# triode_control_board.net
KiCad netlist of a schematic drawn in EAGLE
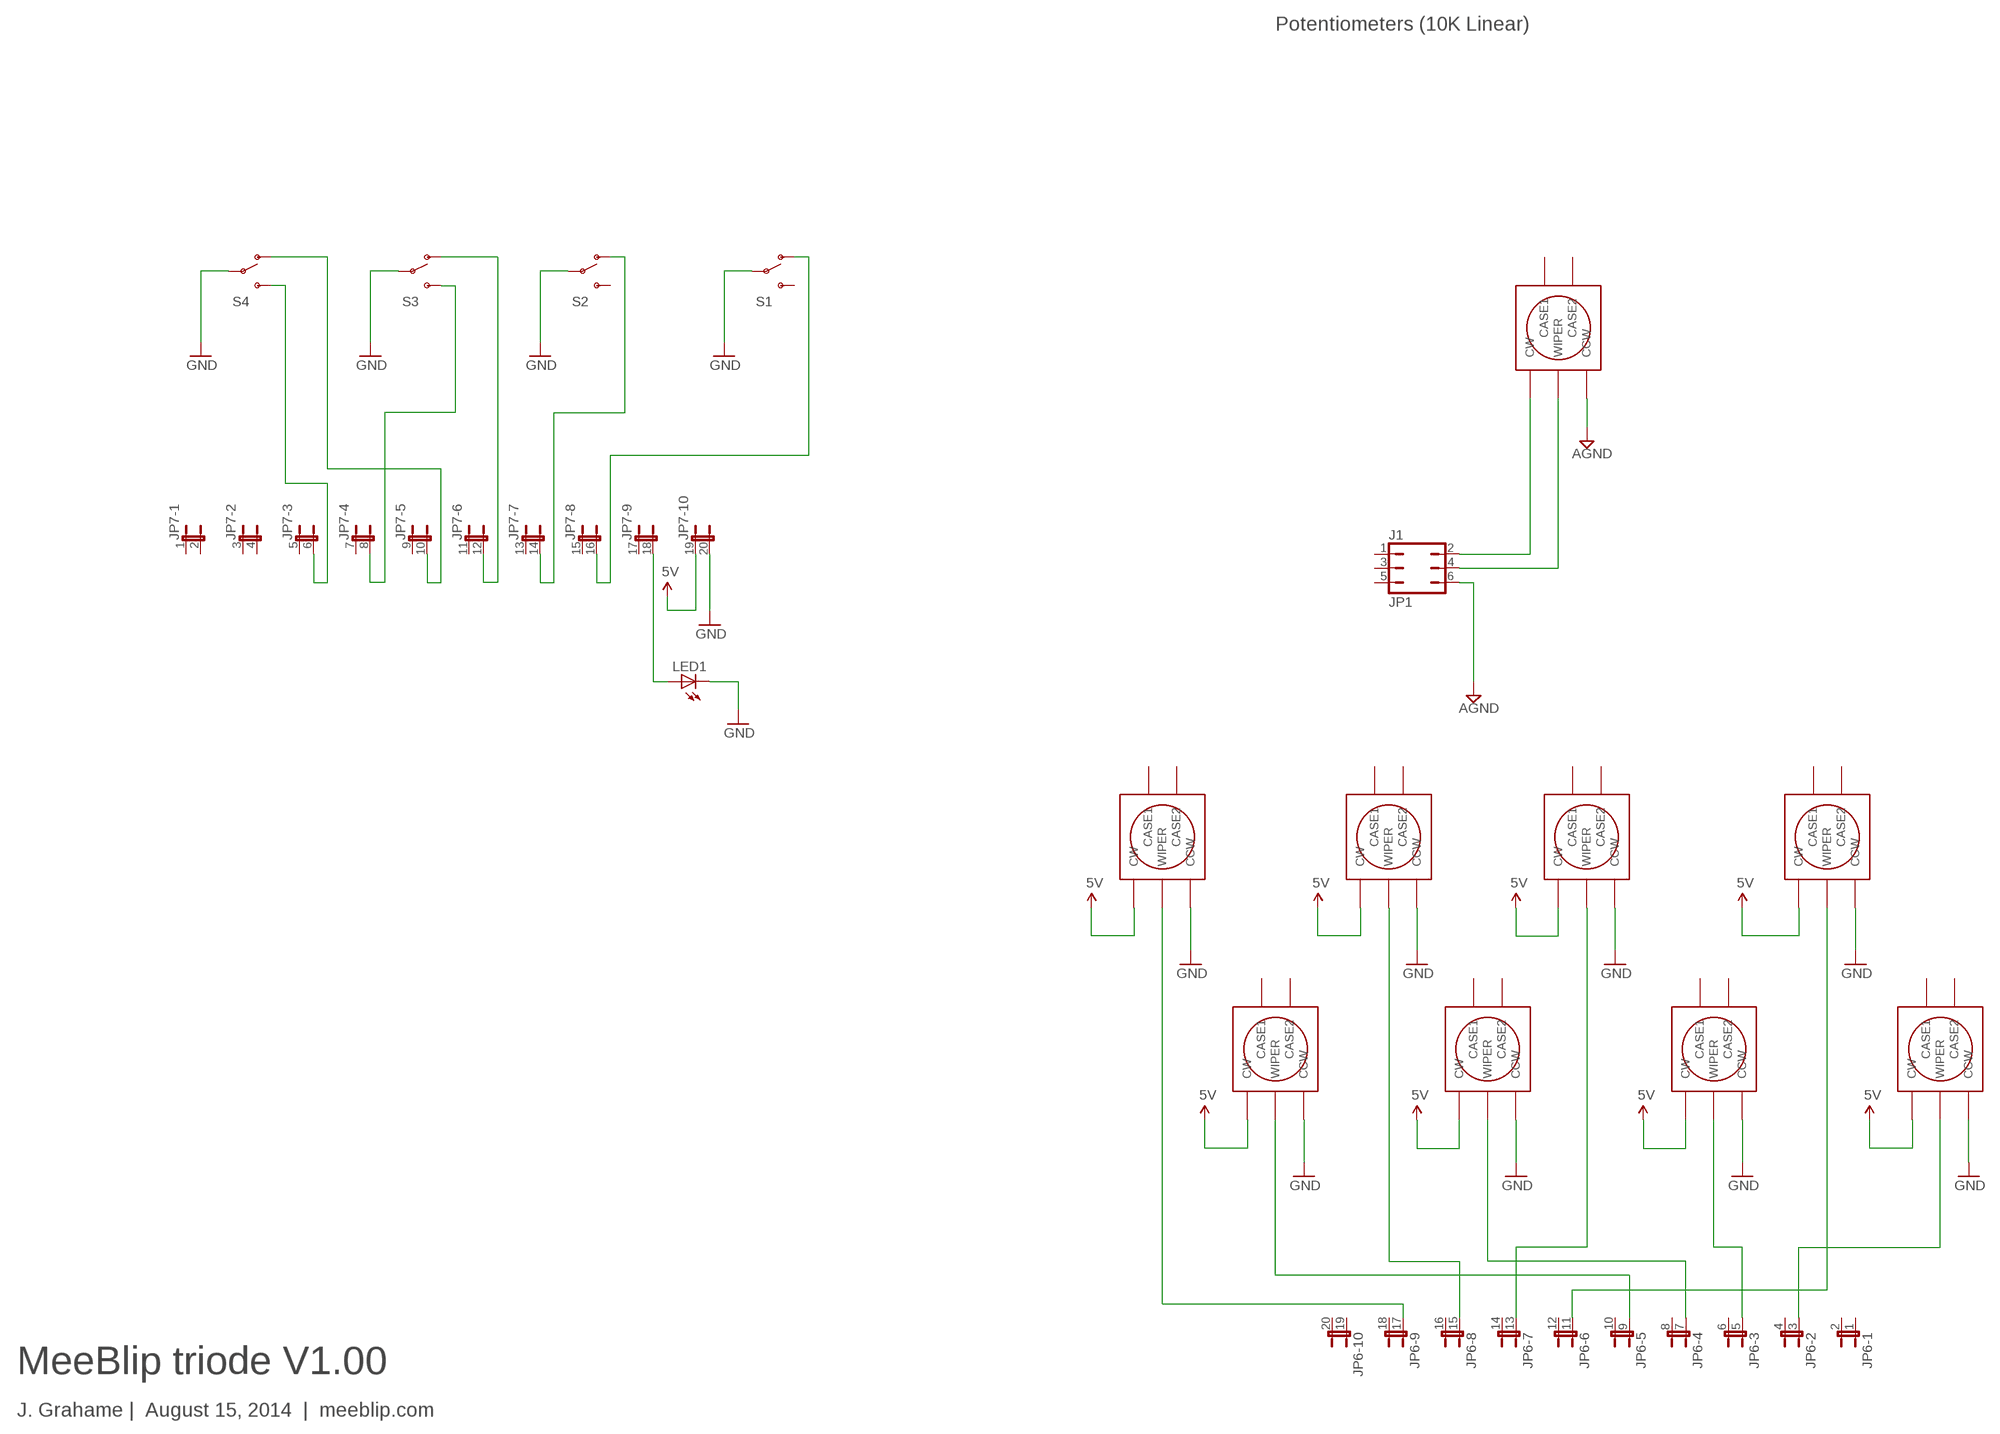
[diagram p0: schematic, sheet 1]

(export (version "E")
  (design (tool "Eeschema 10.0.6"))
  (components
    (comp (ref "J1")
      (value "JP1")
      (footprint "eagle-import:JP3Q")
      (libsource (lib "eagle-import") (part "JP3Q"))
    )
    (comp (ref "JP6")
      (value "JP10QE")
      (footprint "eagle-import:JP10Q")
      (libsource (lib "eagle-import") (part "JP10QE"))
    )
    (comp (ref "JP7")
      (value "JP10QE")
      (footprint "eagle-import:JP10Q")
      (libsource (lib "eagle-import") (part "JP10QE"))
    )
    (comp (ref "LED1")
      (value "LED3MM")
      (footprint "eagle-import:LED3MM")
      (libsource (lib "eagle-import") (part "LED3MM"))
    )
    (comp (ref "POT1")
      (value "VACOLOCO_EVUFRK09_POT")
      (footprint "eagle-import:VACOLOCO_EVUF")
      (libsource (lib "eagle-import") (part "VACOLOCO_EVUFRK09_POT"))
    )
    (comp (ref "POT2")
      (value "VACOLOCO_EVUFRK09_POT")
      (footprint "eagle-import:VACOLOCO_EVUF")
      (libsource (lib "eagle-import") (part "VACOLOCO_EVUFRK09_POT"))
    )
    (comp (ref "POT3")
      (value "VACOLOCO_EVUFRK09_POT")
      (footprint "eagle-import:VACOLOCO_EVUF")
      (libsource (lib "eagle-import") (part "VACOLOCO_EVUFRK09_POT"))
    )
    (comp (ref "POT4")
      (value "VACOLOCO_EVUFRK09_POT")
      (footprint "eagle-import:VACOLOCO_EVUF")
      (libsource (lib "eagle-import") (part "VACOLOCO_EVUFRK09_POT"))
    )
    (comp (ref "POT5")
      (value "VACOLOCO_EVUFRK09_POT")
      (footprint "eagle-import:VACOLOCO_EVUF")
      (libsource (lib "eagle-import") (part "VACOLOCO_EVUFRK09_POT"))
    )
    (comp (ref "POT6")
      (value "VACOLOCO_EVUFRK09_POT")
      (footprint "eagle-import:VACOLOCO_EVUF")
      (libsource (lib "eagle-import") (part "VACOLOCO_EVUFRK09_POT"))
    )
    (comp (ref "POT7")
      (value "VACOLOCO_EVUFRK09_POT")
      (footprint "eagle-import:VACOLOCO_EVUF")
      (libsource (lib "eagle-import") (part "VACOLOCO_EVUFRK09_POT"))
    )
    (comp (ref "POT8")
      (value "VACOLOCO_EVUFRK09_POT")
      (footprint "eagle-import:VACOLOCO_EVUF")
      (libsource (lib "eagle-import") (part "VACOLOCO_EVUFRK09_POT"))
    )
    (comp (ref "POT9")
      (value "VACOLOCO_EVUFRK09_POT")
      (footprint "eagle-import:VACOLOCO_EVUF")
      (libsource (lib "eagle-import") (part "VACOLOCO_EVUFRK09_POT"))
    )
    (comp (ref "S1")
      (value "SWITCH-SPSTMHS122K")
      (footprint "eagle-import:SWITCH-SPDT")
      (libsource (lib "eagle-import") (part "SWITCH-SPSTMHS122K"))
    )
    (comp (ref "S2")
      (value "SWITCH-SPSTMHS122K")
      (footprint "eagle-import:SWITCH-SPDT")
      (libsource (lib "eagle-import") (part "SWITCH-SPSTMHS122K"))
    )
    (comp (ref "S3")
      (value "SWITCH-SPSTMHS122K")
      (footprint "eagle-import:SWITCH-SPDT")
      (libsource (lib "eagle-import") (part "SWITCH-SPSTMHS122K"))
    )
    (comp (ref "S4")
      (value "SWITCH-SPSTMHS122K")
      (footprint "eagle-import:SWITCH-SPDT")
      (libsource (lib "eagle-import") (part "SWITCH-SPSTMHS122K"))
    )
  )
  (nets
    (net (code "1") (name "5V") (class "Default")
      (node (ref "JP7") (pin "19") (pinfunction "1_19") (pintype "passive"))
      (node (ref "POT2") (pin "CW") (pinfunction "CW_CW") (pintype "bidirectional"))
      (node (ref "POT3") (pin "CW") (pinfunction "CW_CW") (pintype "bidirectional"))
      (node (ref "POT4") (pin "CW") (pinfunction "CW_CW") (pintype "bidirectional"))
      (node (ref "POT5") (pin "CW") (pinfunction "CW_CW") (pintype "bidirectional"))
      (node (ref "POT6") (pin "CW") (pinfunction "CW_CW") (pintype "bidirectional"))
      (node (ref "POT7") (pin "CW") (pinfunction "CW_CW") (pintype "bidirectional"))
      (node (ref "POT8") (pin "CW") (pinfunction "CW_CW") (pintype "bidirectional"))
      (node (ref "POT9") (pin "CW") (pinfunction "CW_CW") (pintype "bidirectional"))
    )
    (net (code "2") (name "AGND") (class "Default")
      (node (ref "J1") (pin "6") (pinfunction "6_6") (pintype "passive"))
      (node (ref "POT1") (pin "CCW") (pinfunction "CCW_CCW") (pintype "bidirectional"))
    )
    (net (code "3") (name "GND") (class "Default")
      (node (ref "JP7") (pin "20") (pinfunction "2_20") (pintype "passive"))
      (node (ref "LED1") (pin "K") (pinfunction "C_K") (pintype "passive"))
      (node (ref "POT2") (pin "CCW") (pinfunction "CCW_CCW") (pintype "bidirectional"))
      (node (ref "POT3") (pin "CCW") (pinfunction "CCW_CCW") (pintype "bidirectional"))
      (node (ref "POT4") (pin "CCW") (pinfunction "CCW_CCW") (pintype "bidirectional"))
      (node (ref "POT5") (pin "CCW") (pinfunction "CCW_CCW") (pintype "bidirectional"))
      (node (ref "POT6") (pin "CCW") (pinfunction "CCW_CCW") (pintype "bidirectional"))
      (node (ref "POT7") (pin "CCW") (pinfunction "CCW_CCW") (pintype "bidirectional"))
      (node (ref "POT8") (pin "CCW") (pinfunction "CCW_CCW") (pintype "bidirectional"))
      (node (ref "POT9") (pin "CCW") (pinfunction "CCW_CCW") (pintype "bidirectional"))
      (node (ref "S1") (pin "2") (pinfunction "P_2") (pintype "passive"))
      (node (ref "S2") (pin "2") (pinfunction "P_2") (pintype "passive"))
      (node (ref "S3") (pin "2") (pinfunction "P_2") (pintype "passive"))
      (node (ref "S4") (pin "2") (pinfunction "P_2") (pintype "passive"))
    )
    (net (code "4") (name "Net-(J1-Pad2)") (class "Default")
      (node (ref "J1") (pin "2") (pinfunction "2_2") (pintype "passive"))
      (node (ref "POT1") (pin "CW") (pinfunction "CW_CW") (pintype "bidirectional"))
    )
    (net (code "5") (name "Net-(J1-Pad4)") (class "Default")
      (node (ref "J1") (pin "4") (pinfunction "4_4") (pintype "passive"))
      (node (ref "POT1") (pin "WIPER") (pinfunction "WIPER_WIPER") (pintype "bidirectional"))
    )
    (net (code "6") (name "Net-(JP6C-1)") (class "Default")
      (node (ref "JP6") (pin "3") (pinfunction "1_3") (pintype "passive"))
      (node (ref "POT9") (pin "WIPER") (pinfunction "WIPER_WIPER") (pintype "bidirectional"))
    )
    (net (code "7") (name "Net-(JP6D-1)") (class "Default")
      (node (ref "JP6") (pin "5") (pinfunction "1_5") (pintype "passive"))
      (node (ref "POT8") (pin "WIPER") (pinfunction "WIPER_WIPER") (pintype "bidirectional"))
    )
    (net (code "8") (name "Net-(JP6E-1)") (class "Default")
      (node (ref "JP6") (pin "7") (pinfunction "1_7") (pintype "passive"))
      (node (ref "POT7") (pin "WIPER") (pinfunction "WIPER_WIPER") (pintype "bidirectional"))
    )
    (net (code "9") (name "Net-(JP6F-1)") (class "Default")
      (node (ref "JP6") (pin "9") (pinfunction "1_9") (pintype "passive"))
      (node (ref "POT6") (pin "WIPER") (pinfunction "WIPER_WIPER") (pintype "bidirectional"))
    )
    (net (code "10") (name "Net-(JP6G-1)") (class "Default")
      (node (ref "JP6") (pin "11") (pinfunction "1_11") (pintype "passive"))
      (node (ref "POT5") (pin "WIPER") (pinfunction "WIPER_WIPER") (pintype "bidirectional"))
    )
    (net (code "11") (name "Net-(JP6H-1)") (class "Default")
      (node (ref "JP6") (pin "13") (pinfunction "1_13") (pintype "passive"))
      (node (ref "POT4") (pin "WIPER") (pinfunction "WIPER_WIPER") (pintype "bidirectional"))
    )
    (net (code "12") (name "Net-(JP6I-1)") (class "Default")
      (node (ref "JP6") (pin "15") (pinfunction "1_15") (pintype "passive"))
      (node (ref "POT3") (pin "WIPER") (pinfunction "WIPER_WIPER") (pintype "bidirectional"))
    )
    (net (code "13") (name "Net-(JP6J-1)") (class "Default")
      (node (ref "JP6") (pin "17") (pinfunction "1_17") (pintype "passive"))
      (node (ref "POT2") (pin "WIPER") (pinfunction "WIPER_WIPER") (pintype "bidirectional"))
    )
    (net (code "14") (name "Net-(JP7D-2)") (class "Default")
      (node (ref "JP7") (pin "6") (pinfunction "2_6") (pintype "passive"))
      (node (ref "S4") (pin "3") (pinfunction "S_3") (pintype "passive"))
    )
    (net (code "15") (name "Net-(JP7E-2)") (class "Default")
      (node (ref "JP7") (pin "8") (pinfunction "2_8") (pintype "passive"))
      (node (ref "S3") (pin "3") (pinfunction "S_3") (pintype "passive"))
    )
    (net (code "16") (name "Net-(JP7F-2)") (class "Default")
      (node (ref "JP7") (pin "10") (pinfunction "2_10") (pintype "passive"))
      (node (ref "S4") (pin "1") (pinfunction "O_1") (pintype "passive"))
    )
    (net (code "17") (name "Net-(JP7G-2)") (class "Default")
      (node (ref "JP7") (pin "12") (pinfunction "2_12") (pintype "passive"))
      (node (ref "S3") (pin "1") (pinfunction "O_1") (pintype "passive"))
    )
    (net (code "18") (name "Net-(JP7H-2)") (class "Default")
      (node (ref "JP7") (pin "14") (pinfunction "2_14") (pintype "passive"))
      (node (ref "S2") (pin "1") (pinfunction "O_1") (pintype "passive"))
    )
    (net (code "19") (name "Net-(JP7I-2)") (class "Default")
      (node (ref "JP7") (pin "16") (pinfunction "2_16") (pintype "passive"))
      (node (ref "S1") (pin "1") (pinfunction "O_1") (pintype "passive"))
    )
    (net (code "20") (name "Net-(JP7J-2)") (class "Default")
      (node (ref "JP7") (pin "18") (pinfunction "2_18") (pintype "passive"))
      (node (ref "LED1") (pin "A") (pinfunction "A_A") (pintype "passive"))
    )
    (net (code "21") (name "unconnected-(J1-Pad1)") (class "Default")
      (node (ref "J1") (pin "1") (pinfunction "1_1") (pintype "passive"))
    )
    (net (code "22") (name "unconnected-(J1-Pad3)") (class "Default")
      (node (ref "J1") (pin "3") (pinfunction "3_3") (pintype "passive"))
    )
    (net (code "23") (name "unconnected-(J1-Pad5)") (class "Default")
      (node (ref "J1") (pin "5") (pinfunction "5_5") (pintype "passive"))
    )
    (net (code "24") (name "unconnected-(JP6-Pad1)") (class "Default")
      (node (ref "JP6") (pin "1") (pinfunction "1_1") (pintype "passive"))
    )
    (net (code "25") (name "unconnected-(JP6-Pad2)") (class "Default")
      (node (ref "JP6") (pin "2") (pinfunction "2_2") (pintype "passive"))
    )
    (net (code "26") (name "unconnected-(JP6B-1-Pad19)") (class "Default")
      (node (ref "JP6") (pin "19") (pinfunction "1_19") (pintype "passive"))
    )
    (net (code "27") (name "unconnected-(JP6B-2-Pad20)") (class "Default")
      (node (ref "JP6") (pin "20") (pinfunction "2_20") (pintype "passive"))
    )
    (net (code "28") (name "unconnected-(JP6C-2-Pad4)") (class "Default")
      (node (ref "JP6") (pin "4") (pinfunction "2_4") (pintype "passive"))
    )
    (net (code "29") (name "unconnected-(JP6D-2-Pad6)") (class "Default")
      (node (ref "JP6") (pin "6") (pinfunction "2_6") (pintype "passive"))
    )
    (net (code "30") (name "unconnected-(JP6E-2-Pad8)") (class "Default")
      (node (ref "JP6") (pin "8") (pinfunction "2_8") (pintype "passive"))
    )
    (net (code "31") (name "unconnected-(JP6F-2-Pad10)") (class "Default")
      (node (ref "JP6") (pin "10") (pinfunction "2_10") (pintype "passive"))
    )
    (net (code "32") (name "unconnected-(JP6G-2-Pad12)") (class "Default")
      (node (ref "JP6") (pin "12") (pinfunction "2_12") (pintype "passive"))
    )
    (net (code "33") (name "unconnected-(JP6H-2-Pad14)") (class "Default")
      (node (ref "JP6") (pin "14") (pinfunction "2_14") (pintype "passive"))
    )
    (net (code "34") (name "unconnected-(JP6I-2-Pad16)") (class "Default")
      (node (ref "JP6") (pin "16") (pinfunction "2_16") (pintype "passive"))
    )
    (net (code "35") (name "unconnected-(JP6J-2-Pad18)") (class "Default")
      (node (ref "JP6") (pin "18") (pinfunction "2_18") (pintype "passive"))
    )
    (net (code "36") (name "unconnected-(JP7-Pad1)") (class "Default")
      (node (ref "JP7") (pin "1") (pinfunction "1_1") (pintype "passive"))
    )
    (net (code "37") (name "unconnected-(JP7-Pad2)") (class "Default")
      (node (ref "JP7") (pin "2") (pinfunction "2_2") (pintype "passive"))
    )
    (net (code "38") (name "unconnected-(JP7C-1-Pad3)") (class "Default")
      (node (ref "JP7") (pin "3") (pinfunction "1_3") (pintype "passive"))
    )
    (net (code "39") (name "unconnected-(JP7C-2-Pad4)") (class "Default")
      (node (ref "JP7") (pin "4") (pinfunction "2_4") (pintype "passive"))
    )
    (net (code "40") (name "unconnected-(JP7D-1-Pad5)") (class "Default")
      (node (ref "JP7") (pin "5") (pinfunction "1_5") (pintype "passive"))
    )
    (net (code "41") (name "unconnected-(JP7E-1-Pad7)") (class "Default")
      (node (ref "JP7") (pin "7") (pinfunction "1_7") (pintype "passive"))
    )
    (net (code "42") (name "unconnected-(JP7F-1-Pad9)") (class "Default")
      (node (ref "JP7") (pin "9") (pinfunction "1_9") (pintype "passive"))
    )
    (net (code "43") (name "unconnected-(JP7G-1-Pad11)") (class "Default")
      (node (ref "JP7") (pin "11") (pinfunction "1_11") (pintype "passive"))
    )
    (net (code "44") (name "unconnected-(JP7H-1-Pad13)") (class "Default")
      (node (ref "JP7") (pin "13") (pinfunction "1_13") (pintype "passive"))
    )
    (net (code "45") (name "unconnected-(JP7I-1-Pad15)") (class "Default")
      (node (ref "JP7") (pin "15") (pinfunction "1_15") (pintype "passive"))
    )
    (net (code "46") (name "unconnected-(JP7J-1-Pad17)") (class "Default")
      (node (ref "JP7") (pin "17") (pinfunction "1_17") (pintype "passive"))
    )
    (net (code "47") (name "unconnected-(POT1-PadCASE1)") (class "Default")
      (node (ref "POT1") (pin "CASE1") (pinfunction "CASE1_CASE1") (pintype "bidirectional"))
    )
    (net (code "48") (name "unconnected-(POT1-PadCASE2)") (class "Default")
      (node (ref "POT1") (pin "CASE2") (pinfunction "CASE2_CASE2") (pintype "bidirectional"))
    )
    (net (code "49") (name "unconnected-(POT2-PadCASE1)") (class "Default")
      (node (ref "POT2") (pin "CASE1") (pinfunction "CASE1_CASE1") (pintype "bidirectional"))
    )
    (net (code "50") (name "unconnected-(POT2-PadCASE2)") (class "Default")
      (node (ref "POT2") (pin "CASE2") (pinfunction "CASE2_CASE2") (pintype "bidirectional"))
    )
    (net (code "51") (name "unconnected-(POT3-PadCASE1)") (class "Default")
      (node (ref "POT3") (pin "CASE1") (pinfunction "CASE1_CASE1") (pintype "bidirectional"))
    )
    (net (code "52") (name "unconnected-(POT3-PadCASE2)") (class "Default")
      (node (ref "POT3") (pin "CASE2") (pinfunction "CASE2_CASE2") (pintype "bidirectional"))
    )
    (net (code "53") (name "unconnected-(POT4-PadCASE1)") (class "Default")
      (node (ref "POT4") (pin "CASE1") (pinfunction "CASE1_CASE1") (pintype "bidirectional"))
    )
    (net (code "54") (name "unconnected-(POT4-PadCASE2)") (class "Default")
      (node (ref "POT4") (pin "CASE2") (pinfunction "CASE2_CASE2") (pintype "bidirectional"))
    )
    (net (code "55") (name "unconnected-(POT5-PadCASE1)") (class "Default")
      (node (ref "POT5") (pin "CASE1") (pinfunction "CASE1_CASE1") (pintype "bidirectional"))
    )
    (net (code "56") (name "unconnected-(POT5-PadCASE2)") (class "Default")
      (node (ref "POT5") (pin "CASE2") (pinfunction "CASE2_CASE2") (pintype "bidirectional"))
    )
    (net (code "57") (name "unconnected-(POT6-PadCASE1)") (class "Default")
      (node (ref "POT6") (pin "CASE1") (pinfunction "CASE1_CASE1") (pintype "bidirectional"))
    )
    (net (code "58") (name "unconnected-(POT6-PadCASE2)") (class "Default")
      (node (ref "POT6") (pin "CASE2") (pinfunction "CASE2_CASE2") (pintype "bidirectional"))
    )
    (net (code "59") (name "unconnected-(POT7-PadCASE1)") (class "Default")
      (node (ref "POT7") (pin "CASE1") (pinfunction "CASE1_CASE1") (pintype "bidirectional"))
    )
    (net (code "60") (name "unconnected-(POT7-PadCASE2)") (class "Default")
      (node (ref "POT7") (pin "CASE2") (pinfunction "CASE2_CASE2") (pintype "bidirectional"))
    )
    (net (code "61") (name "unconnected-(POT8-PadCASE1)") (class "Default")
      (node (ref "POT8") (pin "CASE1") (pinfunction "CASE1_CASE1") (pintype "bidirectional"))
    )
    (net (code "62") (name "unconnected-(POT8-PadCASE2)") (class "Default")
      (node (ref "POT8") (pin "CASE2") (pinfunction "CASE2_CASE2") (pintype "bidirectional"))
    )
    (net (code "63") (name "unconnected-(POT9-PadCASE1)") (class "Default")
      (node (ref "POT9") (pin "CASE1") (pinfunction "CASE1_CASE1") (pintype "bidirectional"))
    )
    (net (code "64") (name "unconnected-(POT9-PadCASE2)") (class "Default")
      (node (ref "POT9") (pin "CASE2") (pinfunction "CASE2_CASE2") (pintype "bidirectional"))
    )
    (net (code "65") (name "unconnected-(S1-S-Pad3)") (class "Default")
      (node (ref "S1") (pin "3") (pinfunction "S_3") (pintype "passive"))
    )
    (net (code "66") (name "unconnected-(S2-S-Pad3)") (class "Default")
      (node (ref "S2") (pin "3") (pinfunction "S_3") (pintype "passive"))
    )
  )
)
